# 04_BUTTON.net
KiCad netlist of a schematic drawn in Altium Designer
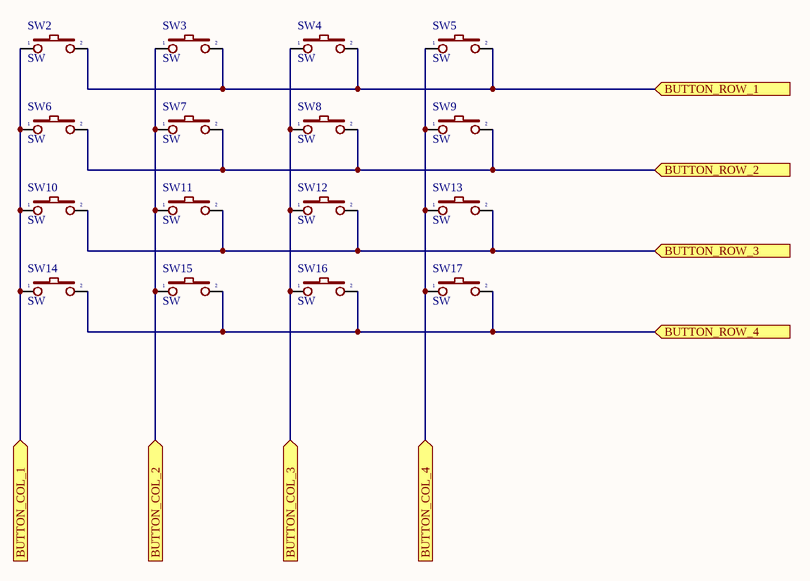
[diagram p0: [04] BUTTON.SchDoc]

(export (version "E")
  (design (tool "Eeschema 10.0.6"))
  (components
    (comp (ref "SW2")
      (value "SW")
      (footprint "SW2")
      (description "Switch button 2 pin")
      (libsource (lib "My Library") (part "SW2"))
    )
    (comp (ref "SW3")
      (value "SW")
      (footprint "SW2")
      (description "Switch button 2 pin")
      (libsource (lib "My Library") (part "SW2"))
    )
    (comp (ref "SW4")
      (value "SW")
      (footprint "SW2")
      (description "Switch button 2 pin")
      (libsource (lib "My Library") (part "SW2"))
    )
    (comp (ref "SW5")
      (value "SW")
      (footprint "SW2")
      (description "Switch button 2 pin")
      (libsource (lib "My Library") (part "SW2"))
    )
    (comp (ref "SW6")
      (value "SW")
      (footprint "SW2")
      (description "Switch button 2 pin")
      (libsource (lib "My Library") (part "SW2"))
    )
    (comp (ref "SW7")
      (value "SW")
      (footprint "SW2")
      (description "Switch button 2 pin")
      (libsource (lib "My Library") (part "SW2"))
    )
    (comp (ref "SW8")
      (value "SW")
      (footprint "SW2")
      (description "Switch button 2 pin")
      (libsource (lib "My Library") (part "SW2"))
    )
    (comp (ref "SW9")
      (value "SW")
      (footprint "SW2")
      (description "Switch button 2 pin")
      (libsource (lib "My Library") (part "SW2"))
    )
    (comp (ref "SW10")
      (value "SW")
      (footprint "SW2")
      (description "Switch button 2 pin")
      (libsource (lib "My Library") (part "SW2"))
    )
    (comp (ref "SW11")
      (value "SW")
      (footprint "SW2")
      (description "Switch button 2 pin")
      (libsource (lib "My Library") (part "SW2"))
    )
    (comp (ref "SW12")
      (value "SW")
      (footprint "SW2")
      (description "Switch button 2 pin")
      (libsource (lib "My Library") (part "SW2"))
    )
    (comp (ref "SW13")
      (value "SW")
      (footprint "SW2")
      (description "Switch button 2 pin")
      (libsource (lib "My Library") (part "SW2"))
    )
    (comp (ref "SW14")
      (value "SW")
      (footprint "SW2")
      (description "Switch button 2 pin")
      (libsource (lib "My Library") (part "SW2"))
    )
    (comp (ref "SW15")
      (value "SW")
      (footprint "SW2")
      (description "Switch button 2 pin")
      (libsource (lib "My Library") (part "SW2"))
    )
    (comp (ref "SW16")
      (value "SW")
      (footprint "SW2")
      (description "Switch button 2 pin")
      (libsource (lib "My Library") (part "SW2"))
    )
    (comp (ref "SW17")
      (value "SW")
      (footprint "SW2")
      (description "Switch button 2 pin")
      (libsource (lib "My Library") (part "SW2"))
    )
  )
  (nets
    (net (code "1") (name "/BUTTON_COL_1") (class "Default")
      (node (ref "SW10") (pin "1") (pinfunction "1_1") (pintype "passive"))
      (node (ref "SW14") (pin "1") (pinfunction "1_1") (pintype "passive"))
      (node (ref "SW2") (pin "1") (pinfunction "1_1") (pintype "passive"))
      (node (ref "SW6") (pin "1") (pinfunction "1_1") (pintype "passive"))
    )
    (net (code "2") (name "/BUTTON_COL_2") (class "Default")
      (node (ref "SW11") (pin "1") (pinfunction "1_1") (pintype "passive"))
      (node (ref "SW15") (pin "1") (pinfunction "1_1") (pintype "passive"))
      (node (ref "SW3") (pin "1") (pinfunction "1_1") (pintype "passive"))
      (node (ref "SW7") (pin "1") (pinfunction "1_1") (pintype "passive"))
    )
    (net (code "3") (name "/BUTTON_COL_3") (class "Default")
      (node (ref "SW12") (pin "1") (pinfunction "1_1") (pintype "passive"))
      (node (ref "SW16") (pin "1") (pinfunction "1_1") (pintype "passive"))
      (node (ref "SW4") (pin "1") (pinfunction "1_1") (pintype "passive"))
      (node (ref "SW8") (pin "1") (pinfunction "1_1") (pintype "passive"))
    )
    (net (code "4") (name "/BUTTON_COL_4") (class "Default")
      (node (ref "SW13") (pin "1") (pinfunction "1_1") (pintype "passive"))
      (node (ref "SW17") (pin "1") (pinfunction "1_1") (pintype "passive"))
      (node (ref "SW5") (pin "1") (pinfunction "1_1") (pintype "passive"))
      (node (ref "SW9") (pin "1") (pinfunction "1_1") (pintype "passive"))
    )
    (net (code "5") (name "/BUTTON_ROW_1") (class "Default")
      (node (ref "SW2") (pin "2") (pinfunction "2_2") (pintype "passive"))
      (node (ref "SW3") (pin "2") (pinfunction "2_2") (pintype "passive"))
      (node (ref "SW4") (pin "2") (pinfunction "2_2") (pintype "passive"))
      (node (ref "SW5") (pin "2") (pinfunction "2_2") (pintype "passive"))
    )
    (net (code "6") (name "/BUTTON_ROW_2") (class "Default")
      (node (ref "SW6") (pin "2") (pinfunction "2_2") (pintype "passive"))
      (node (ref "SW7") (pin "2") (pinfunction "2_2") (pintype "passive"))
      (node (ref "SW8") (pin "2") (pinfunction "2_2") (pintype "passive"))
      (node (ref "SW9") (pin "2") (pinfunction "2_2") (pintype "passive"))
    )
    (net (code "7") (name "/BUTTON_ROW_3") (class "Default")
      (node (ref "SW10") (pin "2") (pinfunction "2_2") (pintype "passive"))
      (node (ref "SW11") (pin "2") (pinfunction "2_2") (pintype "passive"))
      (node (ref "SW12") (pin "2") (pinfunction "2_2") (pintype "passive"))
      (node (ref "SW13") (pin "2") (pinfunction "2_2") (pintype "passive"))
    )
    (net (code "8") (name "/BUTTON_ROW_4") (class "Default")
      (node (ref "SW14") (pin "2") (pinfunction "2_2") (pintype "passive"))
      (node (ref "SW15") (pin "2") (pinfunction "2_2") (pintype "passive"))
      (node (ref "SW16") (pin "2") (pinfunction "2_2") (pintype "passive"))
      (node (ref "SW17") (pin "2") (pinfunction "2_2") (pintype "passive"))
    )
  )
)
